# Fleet-Monitor-CAN-Filter.net
KiCad netlist of a schematic drawn in Altium Designer
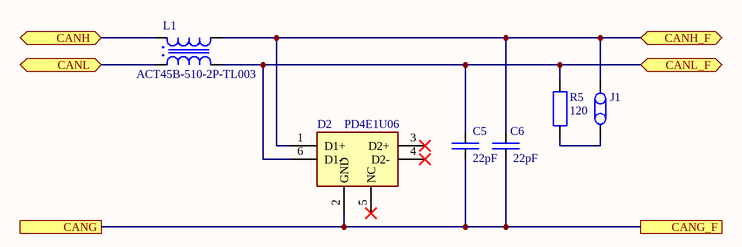
[diagram p0: Fleet-Monitor-CAN-Filter.SchDoc]

(export (version "E")
  (design (tool "Eeschema 10.0.6"))
  (components
    (comp (ref "C5")
      (value "22pF")
      (footprint "SMD Keramikkondensator 0603")
      (description "SMD Ceramic Capacitor E6")
      (libsource (lib "Ceramic Capacitors-E6") (part "E6 - 22pF"))
    )
    (comp (ref "C6")
      (value "22pF")
      (footprint "SMD Keramikkondensator 0603")
      (description "SMD Ceramic Capacitor E6")
      (libsource (lib "Ceramic Capacitors-E6") (part "E6 - 22pF"))
    )
    (comp (ref "D2")
      (value "PD4E1U06")
      (footprint "SMD IC SOT-363 (SC-70-6)")
      (description "Unidirectional 3A (8/20us) 15V (Typ) 6.5V 5.5V (Max) SOT-363 ESD Protection Devices ROHS")
      (libsource (lib "Fleet-Monitor") (part "PD4E1U06DCKR"))
    )
    (comp (ref "J1")
      (value "X-Jumper (2 Fach)")
      (footprint "THT  Jumper")
      (libsource (lib "FakeUSB_KellnCy") (part "X-Jumper (2 Fach)"))
    )
    (comp (ref "L1")
      (value "ACT45B-510-2P-TL003")
      (footprint "SMD Common Mode Choke 4.5x3.2")
      (description "51uH @ 100kHz 2.8kΩ @ 10MHz 50V 1Ω Signal Line 4532 Common Mode Filters ROHS")
      (libsource (lib "Inductors") (part "ACT45B-510-2P-TL003"))
    )
    (comp (ref "R5")
      (value "120")
      (footprint "SMD Widerstand 0603")
      (description "SMD Chip Resistor E24")
      (libsource (lib "Fleet-Monitor") (part "E24 - 120"))
    )
  )
  (nets
    (net (code "1") (name "/CANG") (class "Default")
      (node (ref "C5") (pin "1") (pinfunction "1_1") (pintype "passive"))
      (node (ref "C6") (pin "1") (pinfunction "1_1") (pintype "passive"))
      (node (ref "D2") (pin "2") (pinfunction "GND_2") (pintype "passive"))
    )
    (net (code "2") (name "/CANH") (class "Default")
      (node (ref "L1") (pin "4") (pinfunction "4_4") (pintype "passive"))
    )
    (net (code "3") (name "/CANH_F") (class "Default")
      (node (ref "C6") (pin "2") (pinfunction "2_2") (pintype "passive"))
      (node (ref "D2") (pin "1") (pinfunction "D1+_1") (pintype "passive"))
      (node (ref "J1") (pin "2") (pinfunction "2_2") (pintype "passive"))
      (node (ref "L1") (pin "3") (pinfunction "3_3") (pintype "passive"))
    )
    (net (code "4") (name "/CANL") (class "Default")
      (node (ref "L1") (pin "1") (pinfunction "1_1") (pintype "passive"))
    )
    (net (code "5") (name "/CANL_F") (class "Default")
      (node (ref "C5") (pin "2") (pinfunction "2_2") (pintype "passive"))
      (node (ref "D2") (pin "6") (pinfunction "D1-_6") (pintype "passive"))
      (node (ref "L1") (pin "2") (pinfunction "2_2") (pintype "passive"))
      (node (ref "R5") (pin "2") (pinfunction "2_2") (pintype "passive"))
    )
    (net (code "6") (name "Net-(J1-Pad1)") (class "Default")
      (node (ref "J1") (pin "1") (pinfunction "1_1") (pintype "passive"))
      (node (ref "R5") (pin "1") (pinfunction "1_1") (pintype "passive"))
    )
    (net (code "7") (name "unconnected-(D2-D2+-Pad3)") (class "Default")
      (node (ref "D2") (pin "3") (pinfunction "D2+_3") (pintype "passive+no_connect"))
    )
    (net (code "8") (name "unconnected-(D2-D2--Pad4)") (class "Default")
      (node (ref "D2") (pin "4") (pinfunction "D2-_4") (pintype "passive+no_connect"))
    )
    (net (code "9") (name "unconnected-(D2-NC-Pad5)") (class "Default")
      (node (ref "D2") (pin "5") (pinfunction "NC_5") (pintype "passive+no_connect"))
    )
  )
)
